# uDiplexer_v2.net
KiCad netlist of a schematic drawn in EAGLE
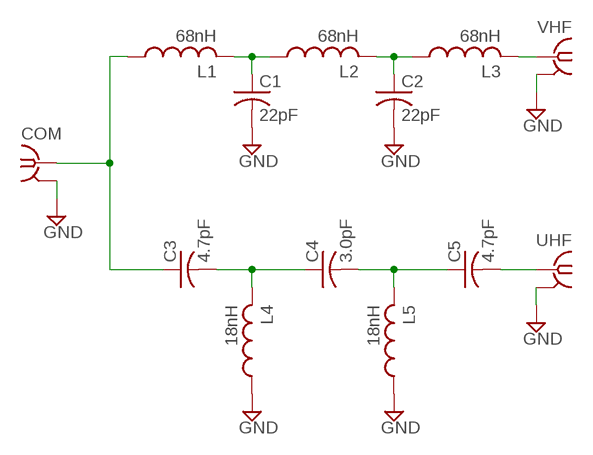
[diagram p0: schematic, sheet 1]

(export (version "E")
  (design (tool "Eeschema 10.0.6"))
  (components
    (comp (ref "C1")
      (value "22pF")
      (footprint "eagle-import:C0805K")
      (libsource (lib "eagle-import") (part "C-USC0805K"))
    )
    (comp (ref "C2")
      (value "22pF")
      (footprint "eagle-import:C0805K")
      (libsource (lib "eagle-import") (part "C-USC0805K"))
    )
    (comp (ref "C3")
      (value "4.7pF")
      (footprint "eagle-import:C0805K")
      (libsource (lib "eagle-import") (part "C-USC0805K"))
    )
    (comp (ref "C4")
      (value "3.0pF")
      (footprint "eagle-import:C0805K")
      (libsource (lib "eagle-import") (part "C-USC0805K"))
    )
    (comp (ref "C5")
      (value "4.7pF")
      (footprint "eagle-import:C0805K")
      (libsource (lib "eagle-import") (part "C-USC0805K"))
    )
    (comp (ref "COM")
      (value "BU-SMA-V")
      (footprint "eagle-import:BU-SMA-V")
      (libsource (lib "eagle-import") (part "BU-SMA-V"))
    )
    (comp (ref "L1")
      (value "68nH")
      (footprint "eagle-import:C0805K")
      (libsource (lib "eagle-import") (part "L-US0805K"))
    )
    (comp (ref "L2")
      (value "68nH")
      (footprint "eagle-import:C0805K")
      (libsource (lib "eagle-import") (part "L-US0805K"))
    )
    (comp (ref "L3")
      (value "68nH")
      (footprint "eagle-import:C0805K")
      (libsource (lib "eagle-import") (part "L-US0805K"))
    )
    (comp (ref "L4")
      (value "18nH")
      (footprint "eagle-import:C0805K")
      (libsource (lib "eagle-import") (part "L-US0805K"))
    )
    (comp (ref "L5")
      (value "18nH")
      (footprint "eagle-import:C0805K")
      (libsource (lib "eagle-import") (part "L-US0805K"))
    )
    (comp (ref "UHF")
      (value "BU-SMA-V")
      (footprint "eagle-import:BU-SMA-V")
      (libsource (lib "eagle-import") (part "BU-SMA-V"))
    )
    (comp (ref "VHF")
      (value "BU-SMA-V")
      (footprint "eagle-import:BU-SMA-V")
      (libsource (lib "eagle-import") (part "BU-SMA-V"))
    )
  )
  (nets
    (net (code "1") (name "GND") (class "Default")
      (node (ref "C1") (pin "2") (pinfunction "2_2") (pintype "passive"))
      (node (ref "C2") (pin "2") (pinfunction "2_2") (pintype "passive"))
      (node (ref "COM") (pin "2") (pinfunction "2_2") (pintype "passive"))
      (node (ref "COM") (pin "3") (pinfunction "2_3") (pintype "passive"))
      (node (ref "COM") (pin "4") (pinfunction "2_4") (pintype "passive"))
      (node (ref "COM") (pin "5") (pinfunction "2_5") (pintype "passive"))
      (node (ref "L4") (pin "1") (pinfunction "1_1") (pintype "passive"))
      (node (ref "L5") (pin "1") (pinfunction "1_1") (pintype "passive"))
      (node (ref "UHF") (pin "2") (pinfunction "2_2") (pintype "passive"))
      (node (ref "UHF") (pin "3") (pinfunction "2_3") (pintype "passive"))
      (node (ref "UHF") (pin "4") (pinfunction "2_4") (pintype "passive"))
      (node (ref "UHF") (pin "5") (pinfunction "2_5") (pintype "passive"))
      (node (ref "VHF") (pin "2") (pinfunction "2_2") (pintype "passive"))
      (node (ref "VHF") (pin "3") (pinfunction "2_3") (pintype "passive"))
      (node (ref "VHF") (pin "4") (pinfunction "2_4") (pintype "passive"))
      (node (ref "VHF") (pin "5") (pinfunction "2_5") (pintype "passive"))
    )
    (net (code "2") (name "Net-(C1-Pad1)") (class "Default")
      (node (ref "C1") (pin "1") (pinfunction "1_1") (pintype "passive"))
      (node (ref "L1") (pin "2") (pinfunction "2_2") (pintype "passive"))
      (node (ref "L2") (pin "1") (pinfunction "1_1") (pintype "passive"))
    )
    (net (code "3") (name "Net-(C2-Pad1)") (class "Default")
      (node (ref "C2") (pin "1") (pinfunction "1_1") (pintype "passive"))
      (node (ref "L2") (pin "2") (pinfunction "2_2") (pintype "passive"))
      (node (ref "L3") (pin "1") (pinfunction "1_1") (pintype "passive"))
    )
    (net (code "4") (name "Net-(C3-Pad1)") (class "Default")
      (node (ref "C3") (pin "1") (pinfunction "1_1") (pintype "passive"))
      (node (ref "COM") (pin "1") (pinfunction "1_1") (pintype "passive"))
      (node (ref "L1") (pin "1") (pinfunction "1_1") (pintype "passive"))
    )
    (net (code "5") (name "Net-(C3-Pad2)") (class "Default")
      (node (ref "C3") (pin "2") (pinfunction "2_2") (pintype "passive"))
      (node (ref "C4") (pin "1") (pinfunction "1_1") (pintype "passive"))
      (node (ref "L4") (pin "2") (pinfunction "2_2") (pintype "passive"))
    )
    (net (code "6") (name "Net-(C4-Pad2)") (class "Default")
      (node (ref "C4") (pin "2") (pinfunction "2_2") (pintype "passive"))
      (node (ref "C5") (pin "1") (pinfunction "1_1") (pintype "passive"))
      (node (ref "L5") (pin "2") (pinfunction "2_2") (pintype "passive"))
    )
    (net (code "7") (name "Net-(C5-Pad2)") (class "Default")
      (node (ref "C5") (pin "2") (pinfunction "2_2") (pintype "passive"))
      (node (ref "UHF") (pin "1") (pinfunction "1_1") (pintype "passive"))
    )
    (net (code "8") (name "Net-(L3-Pad2)") (class "Default")
      (node (ref "L3") (pin "2") (pinfunction "2_2") (pintype "passive"))
      (node (ref "VHF") (pin "1") (pinfunction "1_1") (pintype "passive"))
    )
  )
)
